# p214_1001_001_earth.net
KiCad netlist of a schematic drawn in EAGLE
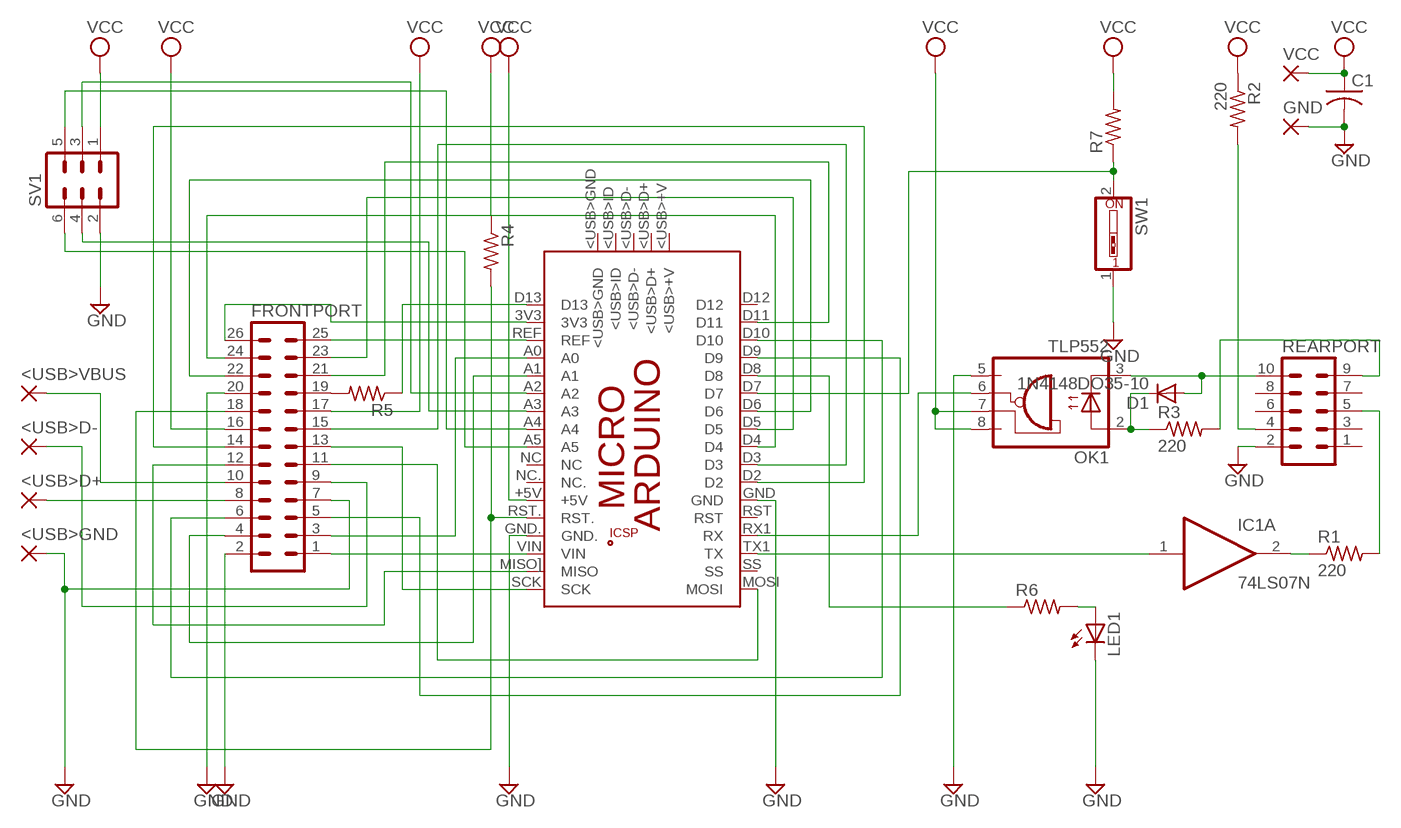
[diagram p0: schematic, sheet 1]

(export (version "E")
  (design (tool "Eeschema 10.0.6"))
  (components
    (comp (ref "<USB>D+")
      (value "1,6/0,9")
      (footprint "eagle-import:1,6_0,9")
      (libsource (lib "eagle-import") (part "1,6/0,9"))
    )
    (comp (ref "<USB>D-")
      (value "1,6/0,9")
      (footprint "eagle-import:1,6_0,9")
      (libsource (lib "eagle-import") (part "1,6/0,9"))
    )
    (comp (ref "<USB>GND")
      (value "1,6/0,9")
      (footprint "eagle-import:1,6_0,9")
      (libsource (lib "eagle-import") (part "1,6/0,9"))
    )
    (comp (ref "<USB>VBUS")
      (value "1,6/0,9")
      (footprint "eagle-import:1,6_0,9")
      (libsource (lib "eagle-import") (part "1,6/0,9"))
    )
    (comp (ref "C1")
      (value "C-US025-025X050")
      (footprint "eagle-import:C025-025X050")
      (libsource (lib "eagle-import") (part "C-US025-025X050"))
    )
    (comp (ref "D1")
      (value "1N4148DO35-10")
      (footprint "eagle-import:DO35-10")
      (libsource (lib "eagle-import") (part "1N4148DO35-10"))
    )
    (comp (ref "FRONTPORT")
      (value "ML26L")
      (footprint "eagle-import:ML26L")
      (libsource (lib "eagle-import") (part "ML26L"))
    )
    (comp (ref "GND")
      (value "1,6/0,9")
      (footprint "eagle-import:1,6_0,9")
      (libsource (lib "eagle-import") (part "1,6/0,9"))
    )
    (comp (ref "IC1")
      (value "74LS07N")
      (footprint "eagle-import:DIL14")
      (libsource (lib "eagle-import") (part "7407NLS"))
    )
    (comp (ref "LED1")
      (value "LED3MM")
      (footprint "eagle-import:LED3MM")
      (libsource (lib "eagle-import") (part "LED3MM"))
    )
    (comp (ref "OK1")
      (value "TLP552")
      (footprint "eagle-import:DIL08")
      (fields (field (name "MPN") "6N137"))
      (libsource (lib "eagle-import") (part "6N137"))
    )
    (comp (ref "PCB1")
      (value "ARDUINO_MICRO")
      (footprint "eagle-import:ARDUINO_MICRO")
      (libsource (lib "eagle-import") (part "ARDUINO_MICRO"))
    )
    (comp (ref "R1")
      (value "220")
      (footprint "eagle-import:0204_7")
      (libsource (lib "eagle-import") (part "R-US_0204/7"))
    )
    (comp (ref "R2")
      (value "220")
      (footprint "eagle-import:0204_7")
      (libsource (lib "eagle-import") (part "R-US_0204/7"))
    )
    (comp (ref "R3")
      (value "220")
      (footprint "eagle-import:0204_7")
      (libsource (lib "eagle-import") (part "R-US_0204/7"))
    )
    (comp (ref "R4")
      (value "R-US_0204/7")
      (footprint "eagle-import:0204_7")
      (libsource (lib "eagle-import") (part "R-US_0204/7"))
    )
    (comp (ref "R5")
      (value "R-US_0204/7")
      (footprint "eagle-import:0204_7")
      (libsource (lib "eagle-import") (part "R-US_0204/7"))
    )
    (comp (ref "R6")
      (value "R-US_0204/7")
      (footprint "eagle-import:0204_7")
      (libsource (lib "eagle-import") (part "R-US_0204/7"))
    )
    (comp (ref "R7")
      (value "R-US_0204/7")
      (footprint "eagle-import:0204_7")
      (libsource (lib "eagle-import") (part "R-US_0204/7"))
    )
    (comp (ref "REARPORT")
      (value "ML10L")
      (footprint "eagle-import:ML10L")
      (libsource (lib "eagle-import") (part "ML10L"))
    )
    (comp (ref "SV1")
      (value "MA03-2")
      (footprint "eagle-import:MA03-2")
      (libsource (lib "eagle-import") (part "MA03-2"))
    )
    (comp (ref "SW1")
      (value "SW_DIP-1")
      (footprint "eagle-import:EDG-01")
      (libsource (lib "eagle-import") (part "SW_DIP-1"))
    )
    (comp (ref "VCC")
      (value "1,6/0,9")
      (footprint "eagle-import:1,6_0,9")
      (libsource (lib "eagle-import") (part "1,6/0,9"))
    )
  )
  (nets
    (net (code "1") (name "GND") (class "Default")
      (node (ref "<USB>GND") (pin "1") (pinfunction "P_1") (pintype "passive"))
      (node (ref "C1") (pin "2") (pinfunction "2_2") (pintype "passive"))
      (node (ref "FRONTPORT") (pin "2") (pinfunction "2_2") (pintype "passive"))
      (node (ref "FRONTPORT") (pin "20") (pinfunction "20_20") (pintype "passive"))
      (node (ref "FRONTPORT") (pin "7") (pinfunction "7_7") (pintype "passive"))
      (node (ref "GND") (pin "1") (pinfunction "P_1") (pintype "passive"))
      (node (ref "LED1") (pin "K") (pinfunction "C_K") (pintype "passive"))
      (node (ref "OK1") (pin "5") (pinfunction "GND_5") (pintype "passive"))
      (node (ref "PCB1") (pin "GND") (pinfunction "GND_GND") (pintype "bidirectional"))
      (node (ref "PCB1") (pin "GND.") (pinfunction "GND._GND.") (pintype "bidirectional"))
      (node (ref "REARPORT") (pin "2") (pinfunction "2_2") (pintype "passive"))
      (node (ref "SV1") (pin "2") (pinfunction "2_2") (pintype "passive"))
      (node (ref "SW1") (pin "1") (pinfunction "1_1") (pintype "passive"))
    )
    (net (code "2") (name "Net-(<USB>D+-P)") (class "Default")
      (node (ref "<USB>D+") (pin "1") (pinfunction "P_1") (pintype "passive"))
      (node (ref "FRONTPORT") (pin "8") (pinfunction "8_8") (pintype "passive"))
    )
    (net (code "3") (name "Net-(<USB>D--P)") (class "Default")
      (node (ref "<USB>D-") (pin "1") (pinfunction "P_1") (pintype "passive"))
      (node (ref "FRONTPORT") (pin "9") (pinfunction "9_9") (pintype "passive"))
    )
    (net (code "4") (name "Net-(<USB>VBUS-P)") (class "Default")
      (node (ref "<USB>VBUS") (pin "1") (pinfunction "P_1") (pintype "passive"))
      (node (ref "FRONTPORT") (pin "10") (pinfunction "10_10") (pintype "passive"))
    )
    (net (code "5") (name "Net-(FRONTPORT-Pad1)") (class "Default")
      (node (ref "FRONTPORT") (pin "1") (pinfunction "1_1") (pintype "passive"))
      (node (ref "PCB1") (pin "VIN") (pinfunction "VIN_VIN") (pintype "bidirectional"))
    )
    (net (code "6") (name "Net-(FRONTPORT-Pad3)") (class "Default")
      (node (ref "FRONTPORT") (pin "3") (pinfunction "3_3") (pintype "passive"))
      (node (ref "PCB1") (pin "A0") (pinfunction "A0_A0") (pintype "bidirectional"))
    )
    (net (code "7") (name "Net-(FRONTPORT-Pad4)") (class "Default")
      (node (ref "FRONTPORT") (pin "4") (pinfunction "4_4") (pintype "passive"))
      (node (ref "PCB1") (pin "A1") (pinfunction "A1_A1") (pintype "bidirectional"))
    )
    (net (code "8") (name "Net-(FRONTPORT-Pad5)") (class "Default")
      (node (ref "FRONTPORT") (pin "5") (pinfunction "5_5") (pintype "passive"))
      (node (ref "PCB1") (pin "D9") (pinfunction "D9_D9") (pintype "bidirectional"))
    )
    (net (code "9") (name "Net-(FRONTPORT-Pad6)") (class "Default")
      (node (ref "FRONTPORT") (pin "6") (pinfunction "6_6") (pintype "passive"))
      (node (ref "PCB1") (pin "D10") (pinfunction "D10_D10") (pintype "bidirectional"))
    )
    (net (code "10") (name "Net-(FRONTPORT-Pad11)") (class "Default")
      (node (ref "FRONTPORT") (pin "11") (pinfunction "11_11") (pintype "passive"))
      (node (ref "PCB1") (pin "MOSI") (pinfunction "MOSI_MOSI") (pintype "bidirectional"))
    )
    (net (code "11") (name "Net-(FRONTPORT-Pad13)") (class "Default")
      (node (ref "FRONTPORT") (pin "13") (pinfunction "13_13") (pintype "passive"))
      (node (ref "PCB1") (pin "SCK") (pinfunction "SCK_SCK") (pintype "bidirectional"))
    )
    (net (code "12") (name "Net-(FRONTPORT-Pad14)") (class "Default")
      (node (ref "FRONTPORT") (pin "14") (pinfunction "14_14") (pintype "passive"))
      (node (ref "PCB1") (pin "D2") (pinfunction "D2_D2") (pintype "bidirectional"))
    )
    (net (code "13") (name "Net-(FRONTPORT-Pad15)") (class "Default")
      (node (ref "FRONTPORT") (pin "15") (pinfunction "15_15") (pintype "passive"))
      (node (ref "PCB1") (pin "D3") (pinfunction "D3_D3") (pintype "bidirectional"))
    )
    (net (code "14") (name "Net-(FRONTPORT-Pad18)") (class "Default")
      (node (ref "FRONTPORT") (pin "18") (pinfunction "18_18") (pintype "passive"))
      (node (ref "PCB1") (pin "RST.") (pinfunction "RST._RST.") (pintype "bidirectional"))
      (node (ref "R4") (pin "2") (pinfunction "2_2") (pintype "passive"))
    )
    (net (code "15") (name "Net-(FRONTPORT-Pad19)") (class "Default")
      (node (ref "FRONTPORT") (pin "19") (pinfunction "19_19") (pintype "passive"))
      (node (ref "R5") (pin "2") (pinfunction "2_2") (pintype "passive"))
    )
    (net (code "16") (name "Net-(FRONTPORT-Pad21)") (class "Default")
      (node (ref "FRONTPORT") (pin "21") (pinfunction "21_21") (pintype "passive"))
      (node (ref "PCB1") (pin "D11") (pinfunction "D11_D11") (pintype "bidirectional"))
    )
    (net (code "17") (name "Net-(FRONTPORT-Pad22)") (class "Default")
      (node (ref "FRONTPORT") (pin "22") (pinfunction "22_22") (pintype "passive"))
      (node (ref "PCB1") (pin "D6") (pinfunction "D6_D6") (pintype "bidirectional"))
    )
    (net (code "18") (name "Net-(FRONTPORT-Pad23)") (class "Default")
      (node (ref "FRONTPORT") (pin "23") (pinfunction "23_23") (pintype "passive"))
      (node (ref "PCB1") (pin "D5") (pinfunction "D5_D5") (pintype "bidirectional"))
    )
    (net (code "19") (name "Net-(FRONTPORT-Pad24)") (class "Default")
      (node (ref "FRONTPORT") (pin "24") (pinfunction "24_24") (pintype "passive"))
      (node (ref "PCB1") (pin "D4") (pinfunction "D4_D4") (pintype "bidirectional"))
    )
    (net (code "20") (name "Net-(FRONTPORT-Pad25)") (class "Default")
      (node (ref "FRONTPORT") (pin "25") (pinfunction "25_25") (pintype "passive"))
      (node (ref "PCB1") (pin "REF") (pinfunction "REF_REF") (pintype "bidirectional"))
    )
    (net (code "21") (name "Net-(FRONTPORT-Pad26)") (class "Default")
      (node (ref "FRONTPORT") (pin "26") (pinfunction "26_26") (pintype "passive"))
      (node (ref "PCB1") (pin "3V3") (pinfunction "3V3_3V3") (pintype "bidirectional"))
    )
    (net (code "22") (name "Net-(IC1A-I)") (class "Default")
      (node (ref "IC1") (pin "1") (pinfunction "I_1") (pintype "input"))
      (node (ref "PCB1") (pin "TX1") (pinfunction "TX_TX1") (pintype "bidirectional"))
    )
    (net (code "23") (name "Net-(IC1A-O)") (class "Default")
      (node (ref "IC1") (pin "2") (pinfunction "O_2") (pintype "open_collector"))
      (node (ref "R1") (pin "1") (pinfunction "1_1") (pintype "passive"))
    )
    (net (code "24") (name "Net-(LED1-PadA)") (class "Default")
      (node (ref "LED1") (pin "A") (pinfunction "A_A") (pintype "passive"))
      (node (ref "R6") (pin "2") (pinfunction "2_2") (pintype "passive"))
    )
    (net (code "25") (name "Net-(OK1-A)") (class "Default")
      (node (ref "D1") (pin "C") (pinfunction "C_C") (pintype "passive"))
      (node (ref "OK1") (pin "2") (pinfunction "A_2") (pintype "passive"))
      (node (ref "R3") (pin "1") (pinfunction "1_1") (pintype "passive"))
    )
    (net (code "26") (name "Net-(OK1-C)") (class "Default")
      (node (ref "D1") (pin "A") (pinfunction "A_A") (pintype "passive"))
      (node (ref "OK1") (pin "3") (pinfunction "C_3") (pintype "passive"))
      (node (ref "REARPORT") (pin "10") (pinfunction "10_10") (pintype "passive"))
    )
    (net (code "27") (name "Net-(OK1-VO)") (class "Default")
      (node (ref "OK1") (pin "6") (pinfunction "VO_6") (pintype "passive"))
      (node (ref "PCB1") (pin "RX1") (pinfunction "RX_RX1") (pintype "bidirectional"))
    )
    (net (code "28") (name "Net-(PCB1-MISO)") (class "Default")
      (node (ref "FRONTPORT") (pin "12") (pinfunction "12_12") (pintype "passive"))
      (node (ref "PCB1") (pin "MISO]") (pinfunction "MISO_MISO]") (pintype "bidirectional"))
    )
    (net (code "29") (name "Net-(PCB1-PadA2)") (class "Default")
      (node (ref "PCB1") (pin "A2") (pinfunction "A2_A2") (pintype "bidirectional"))
      (node (ref "SV1") (pin "3") (pinfunction "3_3") (pintype "passive"))
    )
    (net (code "30") (name "Net-(PCB1-PadA3)") (class "Default")
      (node (ref "PCB1") (pin "A3") (pinfunction "A3_A3") (pintype "bidirectional"))
      (node (ref "SV1") (pin "4") (pinfunction "4_4") (pintype "passive"))
    )
    (net (code "31") (name "Net-(PCB1-PadA4)") (class "Default")
      (node (ref "PCB1") (pin "A4") (pinfunction "A4_A4") (pintype "bidirectional"))
      (node (ref "SV1") (pin "5") (pinfunction "5_5") (pintype "passive"))
    )
    (net (code "32") (name "Net-(PCB1-PadA5)") (class "Default")
      (node (ref "PCB1") (pin "A5") (pinfunction "A5_A5") (pintype "bidirectional"))
      (node (ref "SV1") (pin "6") (pinfunction "6_6") (pintype "passive"))
    )
    (net (code "33") (name "Net-(PCB1-PadD7)") (class "Default")
      (node (ref "PCB1") (pin "D7") (pinfunction "D7_D7") (pintype "bidirectional"))
      (node (ref "R7") (pin "1") (pinfunction "1_1") (pintype "passive"))
      (node (ref "SW1") (pin "2") (pinfunction "2_2") (pintype "passive"))
    )
    (net (code "34") (name "Net-(PCB1-PadD8)") (class "Default")
      (node (ref "PCB1") (pin "D8") (pinfunction "D8_D8") (pintype "bidirectional"))
      (node (ref "R6") (pin "1") (pinfunction "1_1") (pintype "passive"))
    )
    (net (code "35") (name "Net-(PCB1-PadD13)") (class "Default")
      (node (ref "PCB1") (pin "D13") (pinfunction "D13_D13") (pintype "bidirectional"))
      (node (ref "R5") (pin "1") (pinfunction "1_1") (pintype "passive"))
    )
    (net (code "36") (name "Net-(R1-Pad2)") (class "Default")
      (node (ref "R1") (pin "2") (pinfunction "2_2") (pintype "passive"))
      (node (ref "REARPORT") (pin "5") (pinfunction "5_5") (pintype "passive"))
    )
    (net (code "37") (name "Net-(R2-Pad2)") (class "Default")
      (node (ref "R2") (pin "2") (pinfunction "2_2") (pintype "passive"))
      (node (ref "REARPORT") (pin "4") (pinfunction "4_4") (pintype "passive"))
    )
    (net (code "38") (name "Net-(R3-Pad2)") (class "Default")
      (node (ref "R3") (pin "2") (pinfunction "2_2") (pintype "passive"))
      (node (ref "REARPORT") (pin "9") (pinfunction "9_9") (pintype "passive"))
    )
    (net (code "39") (name "VCC") (class "Default")
      (node (ref "C1") (pin "1") (pinfunction "1_1") (pintype "passive"))
      (node (ref "FRONTPORT") (pin "16") (pinfunction "16_16") (pintype "passive"))
      (node (ref "FRONTPORT") (pin "17") (pinfunction "17_17") (pintype "passive"))
      (node (ref "OK1") (pin "7") (pinfunction "VE_7") (pintype "passive"))
      (node (ref "OK1") (pin "8") (pinfunction "VCC_8") (pintype "passive"))
      (node (ref "PCB1") (pin "+5V") (pinfunction "+5V_+5V") (pintype "bidirectional"))
      (node (ref "R2") (pin "1") (pinfunction "1_1") (pintype "passive"))
      (node (ref "R4") (pin "1") (pinfunction "1_1") (pintype "passive"))
      (node (ref "R7") (pin "2") (pinfunction "2_2") (pintype "passive"))
      (node (ref "SV1") (pin "1") (pinfunction "1_1") (pintype "passive"))
      (node (ref "VCC") (pin "1") (pinfunction "P_1") (pintype "passive"))
    )
    (net (code "40") (name "unconnected-(PCB1-Pad5V)") (class "Default")
      (node (ref "PCB1") (pin "5V") (pinfunction "5V_5V") (pintype "bidirectional"))
    )
    (net (code "41") (name "unconnected-(PCB1-Pad<USB>+V)") (class "Default")
      (node (ref "PCB1") (pin "<USB>+V") (pinfunction "<USB>+V_<USB>+V") (pintype "bidirectional"))
    )
    (net (code "42") (name "unconnected-(PCB1-Pad<USB>D+)") (class "Default")
      (node (ref "PCB1") (pin "<USB>D+") (pinfunction "<USB>D+_<USB>D+") (pintype "bidirectional"))
    )
    (net (code "43") (name "unconnected-(PCB1-Pad<USB>D-)") (class "Default")
      (node (ref "PCB1") (pin "<USB>D-") (pinfunction "<USB>D-_<USB>D-") (pintype "bidirectional"))
    )
    (net (code "44") (name "unconnected-(PCB1-Pad<USB>GND)") (class "Default")
      (node (ref "PCB1") (pin "<USB>GND") (pinfunction "<USB>GND_<USB>GND") (pintype "bidirectional"))
    )
    (net (code "45") (name "unconnected-(PCB1-Pad<USB>ID)") (class "Default")
      (node (ref "PCB1") (pin "<USB>ID") (pinfunction "<USB>ID_<USB>ID") (pintype "bidirectional"))
    )
    (net (code "46") (name "unconnected-(PCB1-PadD12)") (class "Default")
      (node (ref "PCB1") (pin "D12") (pinfunction "D12_D12") (pintype "bidirectional"))
    )
    (net (code "47") (name "unconnected-(PCB1-PadGND_)") (class "Default")
      (node (ref "PCB1") (pin "GND_") (pinfunction "GND__GND_") (pintype "bidirectional"))
    )
    (net (code "48") (name "unconnected-(PCB1-PadMISO.)") (class "Default")
      (node (ref "PCB1") (pin "MISO.") (pinfunction "MISO._MISO.") (pintype "bidirectional"))
    )
    (net (code "49") (name "unconnected-(PCB1-PadMOSI.)") (class "Default")
      (node (ref "PCB1") (pin "MOSI.") (pinfunction "MOSI._MOSI.") (pintype "bidirectional"))
    )
    (net (code "50") (name "unconnected-(PCB1-PadNC)") (class "Default")
      (node (ref "PCB1") (pin "NC") (pinfunction "NC_NC") (pintype "bidirectional"))
    )
    (net (code "51") (name "unconnected-(PCB1-PadNC.)") (class "Default")
      (node (ref "PCB1") (pin "NC.") (pinfunction "NC._NC.") (pintype "bidirectional"))
    )
    (net (code "52") (name "unconnected-(PCB1-PadRESET..)") (class "Default")
      (node (ref "PCB1") (pin "RESET..") (pinfunction "RESET.._RESET..") (pintype "bidirectional"))
    )
    (net (code "53") (name "unconnected-(PCB1-PadRST)") (class "Default")
      (node (ref "PCB1") (pin "RST") (pinfunction "RST_RST") (pintype "bidirectional"))
    )
    (net (code "54") (name "unconnected-(PCB1-PadSCK.)") (class "Default")
      (node (ref "PCB1") (pin "SCK.") (pinfunction "SCK._SCK.") (pintype "bidirectional"))
    )
    (net (code "55") (name "unconnected-(PCB1-PadSS)") (class "Default")
      (node (ref "PCB1") (pin "SS") (pinfunction "SS_SS") (pintype "bidirectional"))
    )
    (net (code "56") (name "unconnected-(REARPORT-Pad1)") (class "Default")
      (node (ref "REARPORT") (pin "1") (pinfunction "1_1") (pintype "passive"))
    )
    (net (code "57") (name "unconnected-(REARPORT-Pad3)") (class "Default")
      (node (ref "REARPORT") (pin "3") (pinfunction "3_3") (pintype "passive"))
    )
    (net (code "58") (name "unconnected-(REARPORT-Pad6)") (class "Default")
      (node (ref "REARPORT") (pin "6") (pinfunction "6_6") (pintype "passive"))
    )
    (net (code "59") (name "unconnected-(REARPORT-Pad7)") (class "Default")
      (node (ref "REARPORT") (pin "7") (pinfunction "7_7") (pintype "passive"))
    )
    (net (code "60") (name "unconnected-(REARPORT-Pad8)") (class "Default")
      (node (ref "REARPORT") (pin "8") (pinfunction "8_8") (pintype "passive"))
    )
  )
)
